# HMI_Board.net
KiCad netlist of a schematic drawn in EAGLE
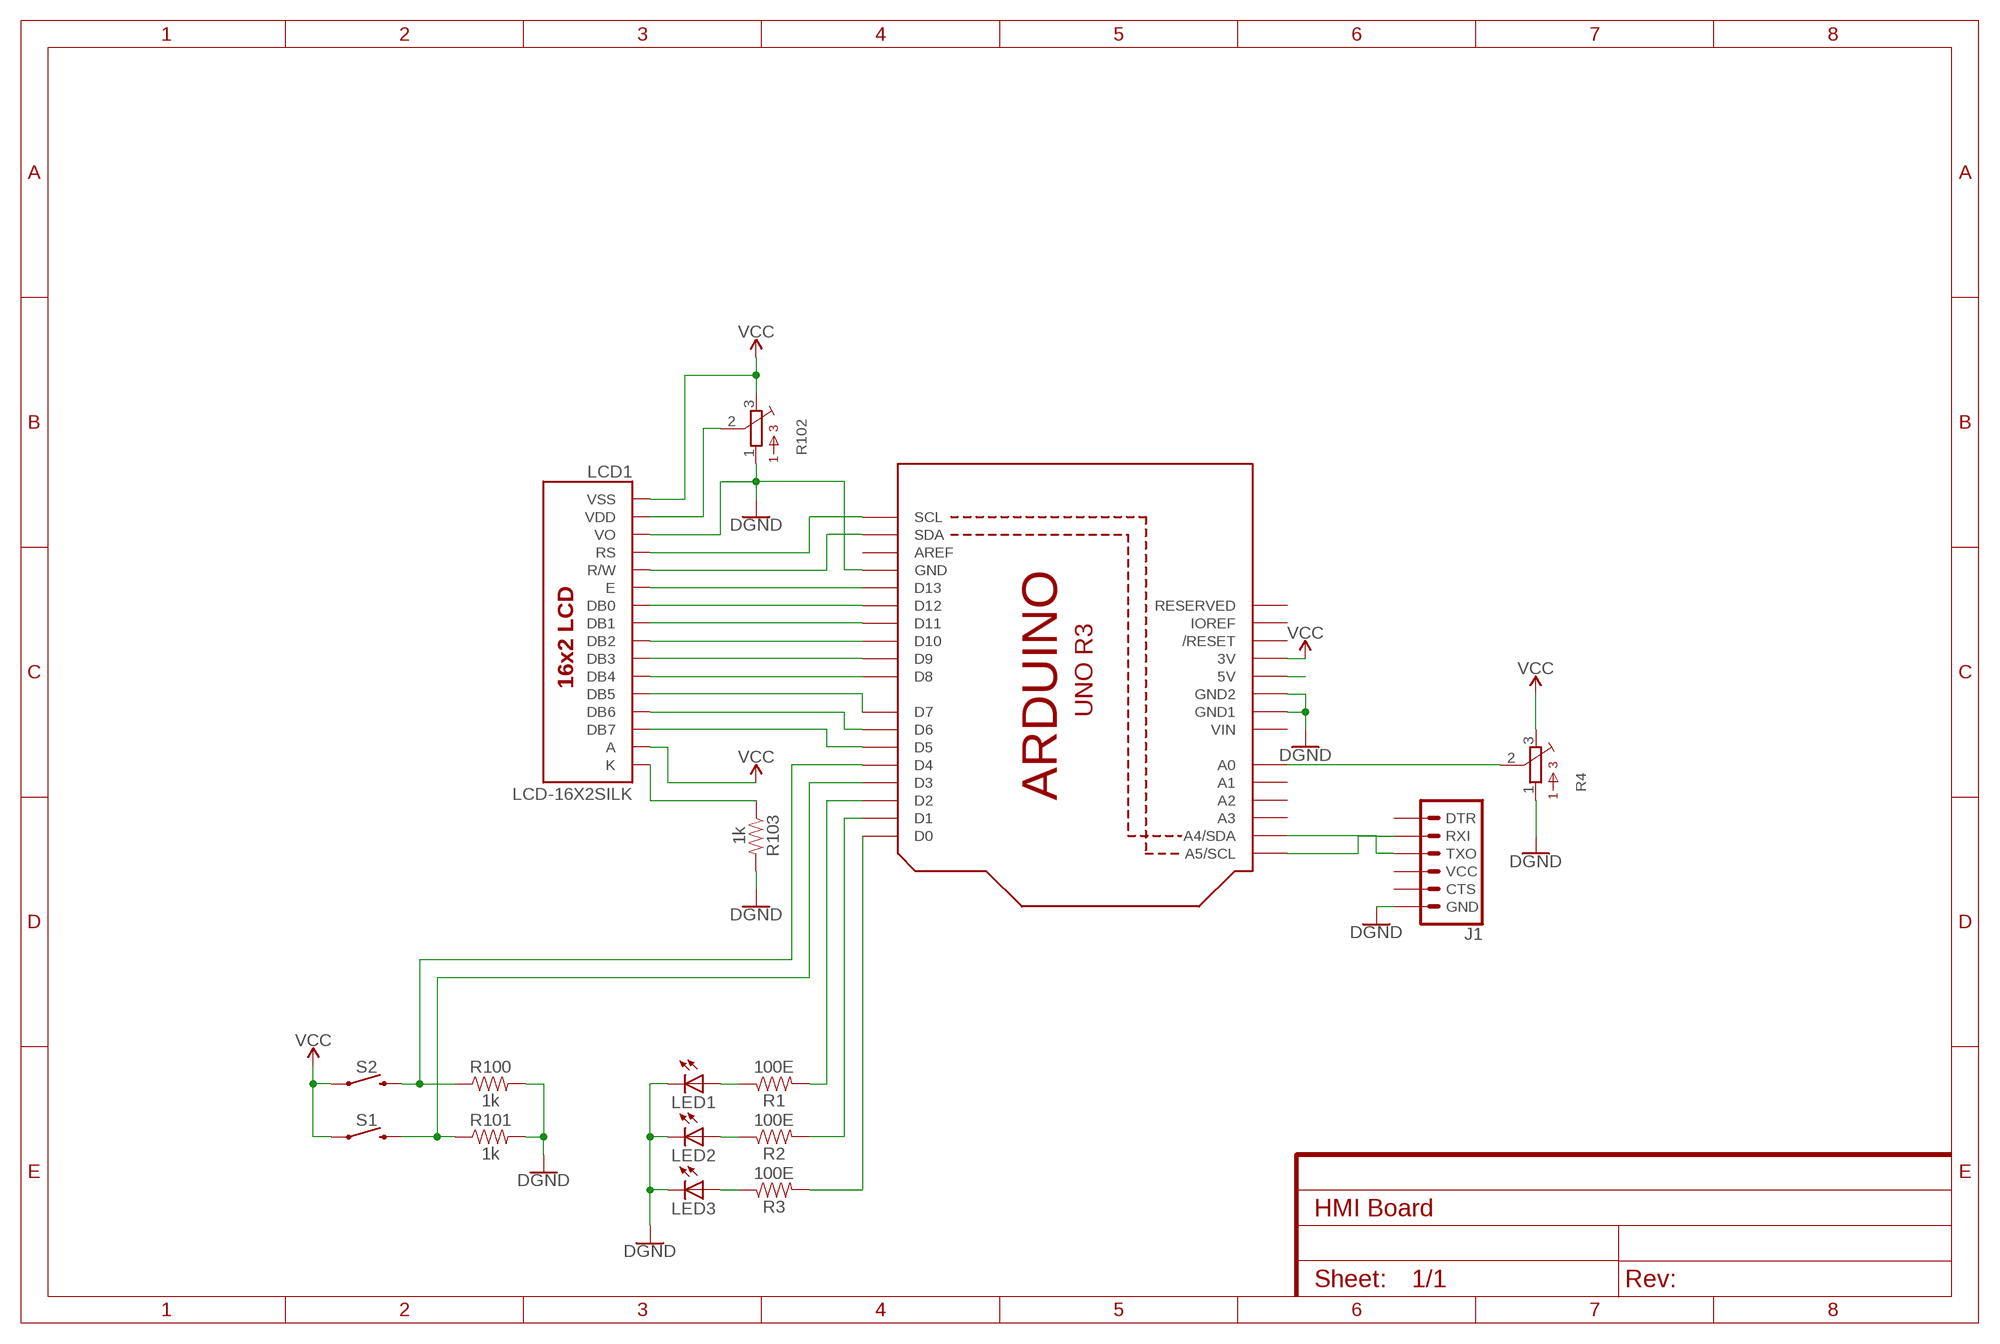
[diagram p0: schematic, sheet 1]

(export (version "E")
  (design (tool "Eeschema 10.0.6"))
  (components
    (comp (ref "J1")
      (value "6_PIN_SERIAL_TARGETLOCK")
      (footprint "eagle-import:1X06_LOCK")
      (libsource (lib "eagle-import") (part "6_PIN_SERIAL_TARGETLOCK"))
    )
    (comp (ref "LCD1")
      (value "LCD-16X2SILK")
      (footprint "eagle-import:LCD-16X2")
      (libsource (lib "eagle-import") (part "LCD-16X2SILK"))
    )
    (comp (ref "LED1")
      (value "LEDCHIP-LED0805")
      (footprint "eagle-import:CHIP-LED0805")
      (libsource (lib "eagle-import") (part "LEDCHIP-LED0805"))
    )
    (comp (ref "LED2")
      (value "LEDCHIP-LED0805")
      (footprint "eagle-import:CHIP-LED0805")
      (libsource (lib "eagle-import") (part "LEDCHIP-LED0805"))
    )
    (comp (ref "LED3")
      (value "LEDCHIP-LED0805")
      (footprint "eagle-import:CHIP-LED0805")
      (libsource (lib "eagle-import") (part "LEDCHIP-LED0805"))
    )
    (comp (ref "R1")
      (value "100E")
      (footprint "eagle-import:0805")
      (libsource (lib "eagle-import") (part "RESISTOR0805"))
    )
    (comp (ref "R2")
      (value "100E")
      (footprint "eagle-import:0805")
      (libsource (lib "eagle-import") (part "RESISTOR0805"))
    )
    (comp (ref "R3")
      (value "100E")
      (footprint "eagle-import:0805")
      (libsource (lib "eagle-import") (part "RESISTOR0805"))
    )
    (comp (ref "R4")
      (value "3386-P")
      (footprint "eagle-import:3386P")
      (libsource (lib "eagle-import") (part "3386-P"))
    )
    (comp (ref "R100")
      (value "1k")
      (footprint "eagle-import:0805")
      (libsource (lib "eagle-import") (part "RESISTOR0805"))
    )
    (comp (ref "R101")
      (value "1k")
      (footprint "eagle-import:0805")
      (libsource (lib "eagle-import") (part "RESISTOR0805"))
    )
    (comp (ref "R102")
      (value "3386-P")
      (footprint "eagle-import:3386P")
      (libsource (lib "eagle-import") (part "3386-P"))
    )
    (comp (ref "R103")
      (value "1k")
      (footprint "eagle-import:0805")
      (libsource (lib "eagle-import") (part "RESISTOR0805"))
    )
    (comp (ref "S1")
      (value "MOMENTARY-SWITCH-SPST-SMD-5.2MM")
      (footprint "eagle-import:TACTILE_SWITCH_SMD_5.2MM")
      (libsource (lib "eagle-import") (part "MOMENTARY-SWITCH-SPST-SMD-5.2MM"))
    )
    (comp (ref "S2")
      (value "MOMENTARY-SWITCH-SPST-SMD-5.2MM")
      (footprint "eagle-import:TACTILE_SWITCH_SMD_5.2MM")
      (libsource (lib "eagle-import") (part "MOMENTARY-SWITCH-SPST-SMD-5.2MM"))
    )
    (comp (ref "U1")
      (value "ARDUINOR3NODIM")
      (footprint "eagle-import:ARDUINOR3-NODIM")
      (libsource (lib "eagle-import") (part "ARDUINOR3NODIM"))
    )
  )
  (nets
    (net (code "1") (name "/VIN") (class "Default")
      (node (ref "U1") (pin "VIN") (pinfunction "VIN_VIN") (pintype "power_in"))
    )
    (net (code "2") (name "DGND") (class "Default")
      (node (ref "J1") (pin "6") (pinfunction "GND_6") (pintype "passive"))
      (node (ref "LCD1") (pin "3") (pinfunction "VO_3") (pintype "bidirectional"))
      (node (ref "LED1") (pin "C") (pinfunction "C_C") (pintype "passive"))
      (node (ref "LED2") (pin "C") (pinfunction "C_C") (pintype "passive"))
      (node (ref "LED3") (pin "C") (pinfunction "C_C") (pintype "passive"))
      (node (ref "R100") (pin "2") (pinfunction "2_2") (pintype "passive"))
      (node (ref "R101") (pin "2") (pinfunction "2_2") (pintype "passive"))
      (node (ref "R102") (pin "1") (pinfunction "1_1") (pintype "passive"))
      (node (ref "R103") (pin "2") (pinfunction "2_2") (pintype "passive"))
      (node (ref "R4") (pin "1") (pinfunction "1_1") (pintype "passive"))
      (node (ref "U1") (pin "GND") (pinfunction "GND_GND") (pintype "power_in"))
      (node (ref "U1") (pin "GND1") (pinfunction "GND1_GND1") (pintype "power_in"))
      (node (ref "U1") (pin "GND2") (pinfunction "GND2_GND2") (pintype "power_in"))
    )
    (net (code "3") (name "Net-(J1-RXI)") (class "Default")
      (node (ref "J1") (pin "2") (pinfunction "RXI_2") (pintype "passive"))
      (node (ref "U1") (pin "A5") (pinfunction "A5/SCL_A5") (pintype "bidirectional"))
    )
    (net (code "4") (name "Net-(J1-TXO)") (class "Default")
      (node (ref "J1") (pin "3") (pinfunction "TXO_3") (pintype "passive"))
      (node (ref "U1") (pin "A4") (pinfunction "A4/SDA_A4") (pintype "bidirectional"))
    )
    (net (code "5") (name "Net-(LCD1-DB0)") (class "Default")
      (node (ref "LCD1") (pin "7") (pinfunction "DB0_7") (pintype "bidirectional"))
      (node (ref "U1") (pin "D12") (pinfunction "D12_D12") (pintype "bidirectional"))
    )
    (net (code "6") (name "Net-(LCD1-DB1)") (class "Default")
      (node (ref "LCD1") (pin "8") (pinfunction "DB1_8") (pintype "bidirectional"))
      (node (ref "U1") (pin "D11") (pinfunction "D11_D11") (pintype "bidirectional"))
    )
    (net (code "7") (name "Net-(LCD1-DB2)") (class "Default")
      (node (ref "LCD1") (pin "9") (pinfunction "DB2_9") (pintype "bidirectional"))
      (node (ref "U1") (pin "D10") (pinfunction "D10_D10") (pintype "bidirectional"))
    )
    (net (code "8") (name "Net-(LCD1-DB3)") (class "Default")
      (node (ref "LCD1") (pin "10") (pinfunction "DB3_10") (pintype "bidirectional"))
      (node (ref "U1") (pin "D9") (pinfunction "D9_D9") (pintype "bidirectional"))
    )
    (net (code "9") (name "Net-(LCD1-DB4)") (class "Default")
      (node (ref "LCD1") (pin "11") (pinfunction "DB4_11") (pintype "bidirectional"))
      (node (ref "U1") (pin "D8") (pinfunction "D8_D8") (pintype "bidirectional"))
    )
    (net (code "10") (name "Net-(LCD1-DB5)") (class "Default")
      (node (ref "LCD1") (pin "12") (pinfunction "DB5_12") (pintype "bidirectional"))
      (node (ref "U1") (pin "D7") (pinfunction "D7_D7") (pintype "bidirectional"))
    )
    (net (code "11") (name "Net-(LCD1-DB6)") (class "Default")
      (node (ref "LCD1") (pin "13") (pinfunction "DB6_13") (pintype "bidirectional"))
      (node (ref "U1") (pin "D6") (pinfunction "D6_D6") (pintype "bidirectional"))
    )
    (net (code "12") (name "Net-(LCD1-DB7)") (class "Default")
      (node (ref "LCD1") (pin "14") (pinfunction "DB7_14") (pintype "bidirectional"))
      (node (ref "U1") (pin "D5") (pinfunction "D5_D5") (pintype "bidirectional"))
    )
    (net (code "13") (name "Net-(LCD1-E)") (class "Default")
      (node (ref "LCD1") (pin "6") (pinfunction "E_6") (pintype "input"))
      (node (ref "U1") (pin "D13") (pinfunction "D13_D13") (pintype "bidirectional"))
    )
    (net (code "14") (name "Net-(LCD1-K)") (class "Default")
      (node (ref "LCD1") (pin "16") (pinfunction "K_16") (pintype "power_in"))
      (node (ref "R103") (pin "1") (pinfunction "1_1") (pintype "passive"))
    )
    (net (code "15") (name "Net-(LCD1-RS)") (class "Default")
      (node (ref "LCD1") (pin "4") (pinfunction "RS_4") (pintype "input"))
      (node (ref "U1") (pin "SCL") (pinfunction "SCL_SCL") (pintype "bidirectional"))
    )
    (net (code "16") (name "Net-(LCD1-R{slash}W)") (class "Default")
      (node (ref "LCD1") (pin "5") (pinfunction "R/W_5") (pintype "input"))
      (node (ref "U1") (pin "SDA") (pinfunction "SDA_SDA") (pintype "bidirectional"))
    )
    (net (code "17") (name "Net-(LCD1-VDD)") (class "Default")
      (node (ref "LCD1") (pin "2") (pinfunction "VDD_2") (pintype "power_in"))
      (node (ref "R102") (pin "2") (pinfunction "2_2") (pintype "passive"))
    )
    (net (code "18") (name "Net-(LED1-PadA)") (class "Default")
      (node (ref "LED1") (pin "A") (pinfunction "A_A") (pintype "passive"))
      (node (ref "R1") (pin "1") (pinfunction "1_1") (pintype "passive"))
    )
    (net (code "19") (name "Net-(LED2-PadA)") (class "Default")
      (node (ref "LED2") (pin "A") (pinfunction "A_A") (pintype "passive"))
      (node (ref "R2") (pin "1") (pinfunction "1_1") (pintype "passive"))
    )
    (net (code "20") (name "Net-(LED3-PadA)") (class "Default")
      (node (ref "LED3") (pin "A") (pinfunction "A_A") (pintype "passive"))
      (node (ref "R3") (pin "1") (pinfunction "1_1") (pintype "passive"))
    )
    (net (code "21") (name "Net-(R1-Pad2)") (class "Default")
      (node (ref "R1") (pin "2") (pinfunction "2_2") (pintype "passive"))
      (node (ref "U1") (pin "D2") (pinfunction "D2_D2") (pintype "bidirectional"))
    )
    (net (code "22") (name "Net-(R2-Pad2)") (class "Default")
      (node (ref "R2") (pin "2") (pinfunction "2_2") (pintype "passive"))
      (node (ref "U1") (pin "D1") (pinfunction "D1_D1") (pintype "bidirectional"))
    )
    (net (code "23") (name "Net-(R3-Pad2)") (class "Default")
      (node (ref "R3") (pin "2") (pinfunction "2_2") (pintype "passive"))
      (node (ref "U1") (pin "D0") (pinfunction "D0_D0") (pintype "bidirectional"))
    )
    (net (code "24") (name "Net-(R4-Pad2)") (class "Default")
      (node (ref "R4") (pin "2") (pinfunction "2_2") (pintype "passive"))
      (node (ref "U1") (pin "A0") (pinfunction "A0_A0") (pintype "bidirectional"))
    )
    (net (code "25") (name "Net-(S1-2)") (class "Default")
      (node (ref "R101") (pin "1") (pinfunction "1_1") (pintype "passive"))
      (node (ref "S1") (pin "3") (pinfunction "2_3") (pintype "passive"))
      (node (ref "U1") (pin "D3") (pinfunction "D3_D3") (pintype "bidirectional"))
    )
    (net (code "26") (name "Net-(S2-2)") (class "Default")
      (node (ref "R100") (pin "1") (pinfunction "1_1") (pintype "passive"))
      (node (ref "S2") (pin "3") (pinfunction "2_3") (pintype "passive"))
      (node (ref "U1") (pin "D4") (pinfunction "D4_D4") (pintype "bidirectional"))
    )
    (net (code "27") (name "VCC") (class "Default")
      (node (ref "LCD1") (pin "1") (pinfunction "VSS_1") (pintype "power_in"))
      (node (ref "LCD1") (pin "15") (pinfunction "A_15") (pintype "power_in"))
      (node (ref "R102") (pin "3") (pinfunction "3_3") (pintype "passive"))
      (node (ref "R4") (pin "3") (pinfunction "3_3") (pintype "passive"))
      (node (ref "S1") (pin "1") (pinfunction "1_1") (pintype "passive"))
      (node (ref "S2") (pin "1") (pinfunction "1_1") (pintype "passive"))
      (node (ref "U1") (pin "3V") (pinfunction "3V_3V") (pintype "power_in"))
    )
    (net (code "28") (name "unconnected-(J1-CTS-Pad5)") (class "Default")
      (node (ref "J1") (pin "5") (pinfunction "CTS_5") (pintype "passive"))
    )
    (net (code "29") (name "unconnected-(J1-DTR-Pad1)") (class "Default")
      (node (ref "J1") (pin "1") (pinfunction "DTR_1") (pintype "passive"))
    )
    (net (code "30") (name "unconnected-(J1-VCC-Pad4)") (class "Default")
      (node (ref "J1") (pin "4") (pinfunction "VCC_4") (pintype "passive"))
    )
    (net (code "31") (name "unconnected-(U1-Pad5V)") (class "Default")
      (node (ref "U1") (pin "5V") (pinfunction "5V_5V") (pintype "power_in"))
    )
    (net (code "32") (name "unconnected-(U1-PadA1)") (class "Default")
      (node (ref "U1") (pin "A1") (pinfunction "A1_A1") (pintype "bidirectional"))
    )
    (net (code "33") (name "unconnected-(U1-PadA2)") (class "Default")
      (node (ref "U1") (pin "A2") (pinfunction "A2_A2") (pintype "bidirectional"))
    )
    (net (code "34") (name "unconnected-(U1-PadA3)") (class "Default")
      (node (ref "U1") (pin "A3") (pinfunction "A3_A3") (pintype "bidirectional"))
    )
    (net (code "35") (name "unconnected-(U1-PadAREF)") (class "Default")
      (node (ref "U1") (pin "AREF") (pinfunction "AREF_AREF") (pintype "bidirectional"))
    )
    (net (code "36") (name "unconnected-(U1-PadIOREF)") (class "Default")
      (node (ref "U1") (pin "IOREF") (pinfunction "IOREF_IOREF") (pintype "output"))
    )
    (net (code "37") (name "unconnected-(U1-PadRESERVED)") (class "Default")
      (node (ref "U1") (pin "RESERVED") (pinfunction "RESERVED_RESERVED") (pintype "no_connect"))
    )
    (net (code "38") (name "unconnected-(U1-{slash}RESET-PadRESET)") (class "Default")
      (node (ref "U1") (pin "RESET") (pinfunction "/RESET_RESET") (pintype "bidirectional"))
    )
  )
)
